# 3x4Matrix.net
KiCad netlist of a schematic drawn in EAGLE
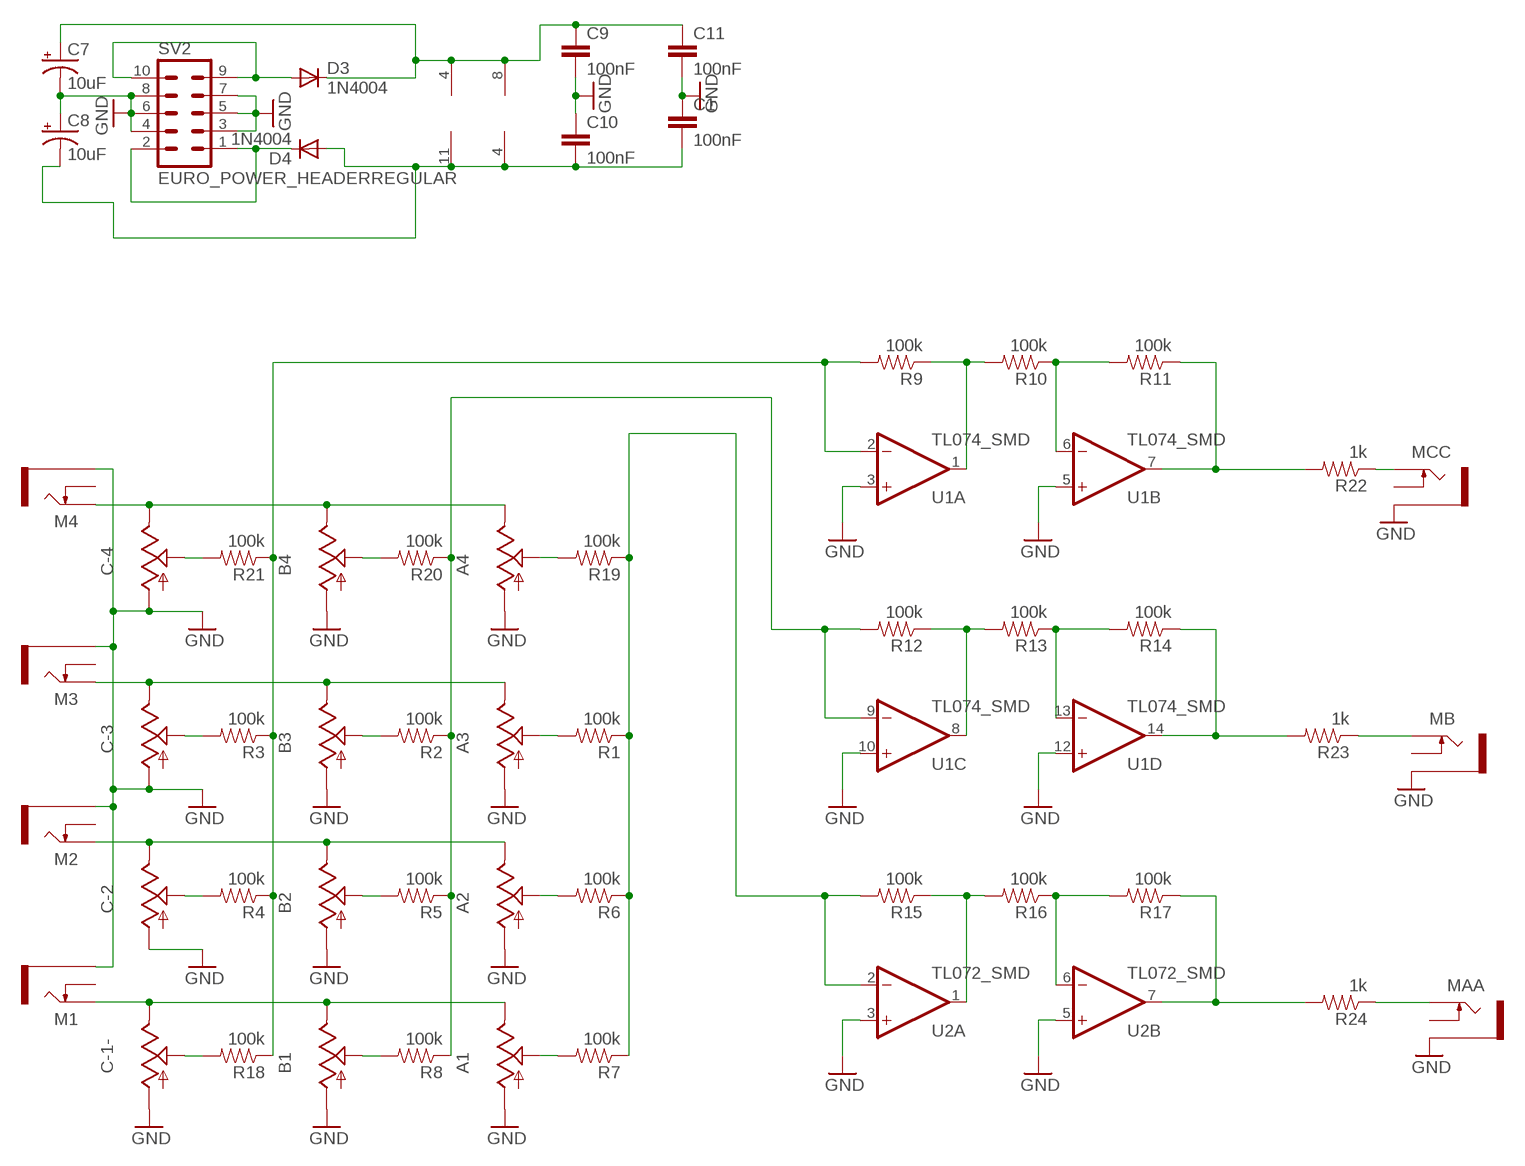
[diagram p0: schematic, sheet 1]

(export (version "E")
  (design (tool "Eeschema 10.0.6"))
  (components
    (comp (ref "A1")
      (value "9MM_SNAP-IN_POT_")
      (footprint "eagle-import:9MM_SNAP-IN_POT")
      (libsource (lib "eagle-import") (part "9MM_SNAP-IN_POT_"))
    )
    (comp (ref "A2")
      (value "9MM_SNAP-IN_POT_")
      (footprint "eagle-import:9MM_SNAP-IN_POT")
      (libsource (lib "eagle-import") (part "9MM_SNAP-IN_POT_"))
    )
    (comp (ref "A3")
      (value "9MM_SNAP-IN_POT_")
      (footprint "eagle-import:9MM_SNAP-IN_POT")
      (libsource (lib "eagle-import") (part "9MM_SNAP-IN_POT_"))
    )
    (comp (ref "A4")
      (value "9MM_SNAP-IN_POT_")
      (footprint "eagle-import:9MM_SNAP-IN_POT")
      (libsource (lib "eagle-import") (part "9MM_SNAP-IN_POT_"))
    )
    (comp (ref "B1")
      (value "9MM_SNAP-IN_POT_")
      (footprint "eagle-import:9MM_SNAP-IN_POT")
      (libsource (lib "eagle-import") (part "9MM_SNAP-IN_POT_"))
    )
    (comp (ref "B2")
      (value "9MM_SNAP-IN_POT_")
      (footprint "eagle-import:9MM_SNAP-IN_POT")
      (libsource (lib "eagle-import") (part "9MM_SNAP-IN_POT_"))
    )
    (comp (ref "B3")
      (value "9MM_SNAP-IN_POT_")
      (footprint "eagle-import:9MM_SNAP-IN_POT")
      (libsource (lib "eagle-import") (part "9MM_SNAP-IN_POT_"))
    )
    (comp (ref "B4")
      (value "9MM_SNAP-IN_POT_")
      (footprint "eagle-import:9MM_SNAP-IN_POT")
      (libsource (lib "eagle-import") (part "9MM_SNAP-IN_POT_"))
    )
    (comp (ref "C-1-")
      (value "9MM_SNAP-IN_POT_")
      (footprint "eagle-import:9MM_SNAP-IN_POT")
      (libsource (lib "eagle-import") (part "9MM_SNAP-IN_POT_"))
    )
    (comp (ref "C-2")
      (value "9MM_SNAP-IN_POT_")
      (footprint "eagle-import:9MM_SNAP-IN_POT")
      (libsource (lib "eagle-import") (part "9MM_SNAP-IN_POT_"))
    )
    (comp (ref "C-3")
      (value "9MM_SNAP-IN_POT_")
      (footprint "eagle-import:9MM_SNAP-IN_POT")
      (libsource (lib "eagle-import") (part "9MM_SNAP-IN_POT_"))
    )
    (comp (ref "C-4")
      (value "9MM_SNAP-IN_POT_")
      (footprint "eagle-import:9MM_SNAP-IN_POT")
      (libsource (lib "eagle-import") (part "9MM_SNAP-IN_POT_"))
    )
    (comp (ref "C1")
      (value "100nF")
      (footprint "eagle-import:0805")
      (libsource (lib "eagle-import") (part "CAP0805"))
    )
    (comp (ref "C7")
      (value "10uF")
      (footprint "eagle-import:CPOL-RADIAL-10UF-25V")
      (libsource (lib "eagle-import") (part "CAP_POLPTH2"))
    )
    (comp (ref "C8")
      (value "10uF")
      (footprint "eagle-import:CPOL-RADIAL-10UF-25V")
      (libsource (lib "eagle-import") (part "CAP_POLPTH2"))
    )
    (comp (ref "C9")
      (value "100nF")
      (footprint "eagle-import:0805")
      (libsource (lib "eagle-import") (part "CAP0805"))
    )
    (comp (ref "C10")
      (value "100nF")
      (footprint "eagle-import:0805")
      (libsource (lib "eagle-import") (part "CAP0805"))
    )
    (comp (ref "C11")
      (value "100nF")
      (footprint "eagle-import:0805")
      (libsource (lib "eagle-import") (part "CAP0805"))
    )
    (comp (ref "D3")
      (value "1N4004")
      (footprint "eagle-import:DO41-10")
      (libsource (lib "eagle-import") (part "1N4004"))
    )
    (comp (ref "D4")
      (value "1N4004")
      (footprint "eagle-import:DO41-10")
      (libsource (lib "eagle-import") (part "1N4004"))
    )
    (comp (ref "M1")
      (value "THONKICONNNEW")
      (footprint "eagle-import:WQP-PJ301M-12_JACK")
      (libsource (lib "eagle-import") (part "THONKICONNNEW"))
    )
    (comp (ref "M2")
      (value "THONKICONNNEW")
      (footprint "eagle-import:WQP-PJ301M-12_JACK")
      (libsource (lib "eagle-import") (part "THONKICONNNEW"))
    )
    (comp (ref "M3")
      (value "THONKICONNNEW")
      (footprint "eagle-import:WQP-PJ301M-12_JACK")
      (libsource (lib "eagle-import") (part "THONKICONNNEW"))
    )
    (comp (ref "M4")
      (value "THONKICONNNEW")
      (footprint "eagle-import:WQP-PJ301M-12_JACK")
      (libsource (lib "eagle-import") (part "THONKICONNNEW"))
    )
    (comp (ref "MAA")
      (value "THONKICONNNEW")
      (footprint "eagle-import:WQP-PJ301M-12_JACK")
      (libsource (lib "eagle-import") (part "THONKICONNNEW"))
    )
    (comp (ref "MB")
      (value "THONKICONNNEW")
      (footprint "eagle-import:WQP-PJ301M-12_JACK")
      (libsource (lib "eagle-import") (part "THONKICONNNEW"))
    )
    (comp (ref "MCC")
      (value "THONKICONNNEW")
      (footprint "eagle-import:WQP-PJ301M-12_JACK")
      (libsource (lib "eagle-import") (part "THONKICONNNEW"))
    )
    (comp (ref "R1")
      (value "100k")
      (footprint "eagle-import:0805")
      (libsource (lib "eagle-import") (part "RESISTOR0805-RES"))
    )
    (comp (ref "R2")
      (value "100k")
      (footprint "eagle-import:0805")
      (libsource (lib "eagle-import") (part "RESISTOR0805-RES"))
    )
    (comp (ref "R3")
      (value "100k")
      (footprint "eagle-import:0805")
      (libsource (lib "eagle-import") (part "RESISTOR0805-RES"))
    )
    (comp (ref "R4")
      (value "100k")
      (footprint "eagle-import:0805")
      (libsource (lib "eagle-import") (part "RESISTOR0805-RES"))
    )
    (comp (ref "R5")
      (value "100k")
      (footprint "eagle-import:0805")
      (libsource (lib "eagle-import") (part "RESISTOR0805-RES"))
    )
    (comp (ref "R6")
      (value "100k")
      (footprint "eagle-import:0805")
      (libsource (lib "eagle-import") (part "RESISTOR0805-RES"))
    )
    (comp (ref "R7")
      (value "100k")
      (footprint "eagle-import:0805")
      (libsource (lib "eagle-import") (part "RESISTOR0805-RES"))
    )
    (comp (ref "R8")
      (value "100k")
      (footprint "eagle-import:0805")
      (libsource (lib "eagle-import") (part "RESISTOR0805-RES"))
    )
    (comp (ref "R9")
      (value "100k")
      (footprint "eagle-import:0805")
      (libsource (lib "eagle-import") (part "RESISTOR0805-RES"))
    )
    (comp (ref "R10")
      (value "100k")
      (footprint "eagle-import:0805")
      (libsource (lib "eagle-import") (part "RESISTOR0805-RES"))
    )
    (comp (ref "R11")
      (value "100k")
      (footprint "eagle-import:0805")
      (libsource (lib "eagle-import") (part "RESISTOR0805-RES"))
    )
    (comp (ref "R12")
      (value "100k")
      (footprint "eagle-import:0805")
      (libsource (lib "eagle-import") (part "RESISTOR0805-RES"))
    )
    (comp (ref "R13")
      (value "100k")
      (footprint "eagle-import:0805")
      (libsource (lib "eagle-import") (part "RESISTOR0805-RES"))
    )
    (comp (ref "R14")
      (value "100k")
      (footprint "eagle-import:0805")
      (libsource (lib "eagle-import") (part "RESISTOR0805-RES"))
    )
    (comp (ref "R15")
      (value "100k")
      (footprint "eagle-import:0805")
      (libsource (lib "eagle-import") (part "RESISTOR0805-RES"))
    )
    (comp (ref "R16")
      (value "100k")
      (footprint "eagle-import:0805")
      (libsource (lib "eagle-import") (part "RESISTOR0805-RES"))
    )
    (comp (ref "R17")
      (value "100k")
      (footprint "eagle-import:0805")
      (libsource (lib "eagle-import") (part "RESISTOR0805-RES"))
    )
    (comp (ref "R18")
      (value "100k")
      (footprint "eagle-import:0805")
      (libsource (lib "eagle-import") (part "RESISTOR0805-RES"))
    )
    (comp (ref "R19")
      (value "100k")
      (footprint "eagle-import:0805")
      (libsource (lib "eagle-import") (part "RESISTOR0805-RES"))
    )
    (comp (ref "R20")
      (value "100k")
      (footprint "eagle-import:0805")
      (libsource (lib "eagle-import") (part "RESISTOR0805-RES"))
    )
    (comp (ref "R21")
      (value "100k")
      (footprint "eagle-import:0805")
      (libsource (lib "eagle-import") (part "RESISTOR0805-RES"))
    )
    (comp (ref "R22")
      (value "1k")
      (footprint "eagle-import:0805")
      (libsource (lib "eagle-import") (part "RESISTOR0805-RES"))
    )
    (comp (ref "R23")
      (value "1k")
      (footprint "eagle-import:0805")
      (libsource (lib "eagle-import") (part "RESISTOR0805-RES"))
    )
    (comp (ref "R24")
      (value "1k")
      (footprint "eagle-import:0805")
      (libsource (lib "eagle-import") (part "RESISTOR0805-RES"))
    )
    (comp (ref "SV2")
      (value "EURO_POWER_HEADERREGULAR")
      (footprint "eagle-import:EURO_POWER_HEADER")
      (libsource (lib "eagle-import") (part "EURO_POWER_HEADERREGULAR"))
    )
    (comp (ref "U1")
      (value "TL074_SMD")
      (footprint "eagle-import:SO14")
      (libsource (lib "eagle-import") (part "TL074_SMD"))
    )
    (comp (ref "U2")
      (value "TL072_SMD")
      (footprint "eagle-import:SO08")
      (libsource (lib "eagle-import") (part "TL072_SMD"))
    )
  )
  (nets
    (net (code "1") (name "GND") (class "Default")
      (node (ref "A1") (pin "1") (pinfunction "A_1") (pintype "passive"))
      (node (ref "A2") (pin "1") (pinfunction "A_1") (pintype "passive"))
      (node (ref "A3") (pin "1") (pinfunction "A_1") (pintype "passive"))
      (node (ref "A4") (pin "1") (pinfunction "A_1") (pintype "passive"))
      (node (ref "B1") (pin "1") (pinfunction "A_1") (pintype "passive"))
      (node (ref "B2") (pin "1") (pinfunction "A_1") (pintype "passive"))
      (node (ref "B3") (pin "1") (pinfunction "A_1") (pintype "passive"))
      (node (ref "B4") (pin "1") (pinfunction "A_1") (pintype "passive"))
      (node (ref "C-1-") (pin "1") (pinfunction "A_1") (pintype "passive"))
      (node (ref "C-2") (pin "1") (pinfunction "A_1") (pintype "passive"))
      (node (ref "C-3") (pin "1") (pinfunction "A_1") (pintype "passive"))
      (node (ref "C-4") (pin "1") (pinfunction "A_1") (pintype "passive"))
      (node (ref "C1") (pin "1") (pinfunction "1_1") (pintype "passive"))
      (node (ref "C10") (pin "1") (pinfunction "1_1") (pintype "passive"))
      (node (ref "C11") (pin "2") (pinfunction "2_2") (pintype "passive"))
      (node (ref "C7") (pin "2") (pinfunction "-_2") (pintype "passive"))
      (node (ref "C8") (pin "1") (pinfunction "+_1") (pintype "passive"))
      (node (ref "C9") (pin "2") (pinfunction "2_2") (pintype "passive"))
      (node (ref "M1") (pin "P$3_SLEEVE") (pinfunction "SLEEVE_P$3_SLEEVE") (pintype "passive"))
      (node (ref "M2") (pin "P$3_SLEEVE") (pinfunction "SLEEVE_P$3_SLEEVE") (pintype "passive"))
      (node (ref "M3") (pin "P$3_SLEEVE") (pinfunction "SLEEVE_P$3_SLEEVE") (pintype "passive"))
      (node (ref "M4") (pin "P$3_SLEEVE") (pinfunction "SLEEVE_P$3_SLEEVE") (pintype "passive"))
      (node (ref "MAA") (pin "P$3_SLEEVE") (pinfunction "SLEEVE_P$3_SLEEVE") (pintype "passive"))
      (node (ref "MB") (pin "P$3_SLEEVE") (pinfunction "SLEEVE_P$3_SLEEVE") (pintype "passive"))
      (node (ref "MCC") (pin "P$3_SLEEVE") (pinfunction "SLEEVE_P$3_SLEEVE") (pintype "passive"))
      (node (ref "SV2") (pin "3") (pinfunction "3_3") (pintype "passive"))
      (node (ref "SV2") (pin "4") (pinfunction "4_4") (pintype "passive"))
      (node (ref "SV2") (pin "5") (pinfunction "5_5") (pintype "passive"))
      (node (ref "SV2") (pin "6") (pinfunction "6_6") (pintype "passive"))
      (node (ref "SV2") (pin "7") (pinfunction "7_7") (pintype "passive"))
      (node (ref "SV2") (pin "8") (pinfunction "8_8") (pintype "passive"))
      (node (ref "U1") (pin "10") (pinfunction "+IN_10") (pintype "input"))
      (node (ref "U1") (pin "12") (pinfunction "+IN_12") (pintype "input"))
      (node (ref "U1") (pin "3") (pinfunction "+IN_3") (pintype "input"))
      (node (ref "U1") (pin "5") (pinfunction "+IN_5") (pintype "input"))
      (node (ref "U2") (pin "3") (pinfunction "+IN_3") (pintype "input"))
      (node (ref "U2") (pin "5") (pinfunction "+IN_5") (pintype "input"))
    )
    (net (code "2") (name "Net-(A1-E)") (class "Default")
      (node (ref "A1") (pin "3") (pinfunction "E_3") (pintype "passive"))
      (node (ref "B1") (pin "3") (pinfunction "E_3") (pintype "passive"))
      (node (ref "C-1-") (pin "3") (pinfunction "E_3") (pintype "passive"))
      (node (ref "M1") (pin "P$1_TIP") (pinfunction "TIP_P$1_TIP") (pintype "passive"))
    )
    (net (code "3") (name "Net-(A1-S)") (class "Default")
      (node (ref "A1") (pin "2") (pinfunction "S_2") (pintype "passive"))
      (node (ref "R7") (pin "2") (pinfunction "2_2") (pintype "passive"))
    )
    (net (code "4") (name "Net-(A2-E)") (class "Default")
      (node (ref "A2") (pin "3") (pinfunction "E_3") (pintype "passive"))
      (node (ref "B2") (pin "3") (pinfunction "E_3") (pintype "passive"))
      (node (ref "C-2") (pin "3") (pinfunction "E_3") (pintype "passive"))
      (node (ref "M2") (pin "P$1_TIP") (pinfunction "TIP_P$1_TIP") (pintype "passive"))
    )
    (net (code "5") (name "Net-(A2-S)") (class "Default")
      (node (ref "A2") (pin "2") (pinfunction "S_2") (pintype "passive"))
      (node (ref "R6") (pin "2") (pinfunction "2_2") (pintype "passive"))
    )
    (net (code "6") (name "Net-(A3-E)") (class "Default")
      (node (ref "A3") (pin "3") (pinfunction "E_3") (pintype "passive"))
      (node (ref "B3") (pin "3") (pinfunction "E_3") (pintype "passive"))
      (node (ref "C-3") (pin "3") (pinfunction "E_3") (pintype "passive"))
      (node (ref "M3") (pin "P$1_TIP") (pinfunction "TIP_P$1_TIP") (pintype "passive"))
    )
    (net (code "7") (name "Net-(A3-S)") (class "Default")
      (node (ref "A3") (pin "2") (pinfunction "S_2") (pintype "passive"))
      (node (ref "R1") (pin "2") (pinfunction "2_2") (pintype "passive"))
    )
    (net (code "8") (name "Net-(A4-E)") (class "Default")
      (node (ref "A4") (pin "3") (pinfunction "E_3") (pintype "passive"))
      (node (ref "B4") (pin "3") (pinfunction "E_3") (pintype "passive"))
      (node (ref "C-4") (pin "3") (pinfunction "E_3") (pintype "passive"))
      (node (ref "M4") (pin "P$1_TIP") (pinfunction "TIP_P$1_TIP") (pintype "passive"))
    )
    (net (code "9") (name "Net-(A4-S)") (class "Default")
      (node (ref "A4") (pin "2") (pinfunction "S_2") (pintype "passive"))
      (node (ref "R19") (pin "2") (pinfunction "2_2") (pintype "passive"))
    )
    (net (code "10") (name "Net-(B1-S)") (class "Default")
      (node (ref "B1") (pin "2") (pinfunction "S_2") (pintype "passive"))
      (node (ref "R8") (pin "2") (pinfunction "2_2") (pintype "passive"))
    )
    (net (code "11") (name "Net-(B2-S)") (class "Default")
      (node (ref "B2") (pin "2") (pinfunction "S_2") (pintype "passive"))
      (node (ref "R5") (pin "2") (pinfunction "2_2") (pintype "passive"))
    )
    (net (code "12") (name "Net-(B3-S)") (class "Default")
      (node (ref "B3") (pin "2") (pinfunction "S_2") (pintype "passive"))
      (node (ref "R2") (pin "2") (pinfunction "2_2") (pintype "passive"))
    )
    (net (code "13") (name "Net-(B4-S)") (class "Default")
      (node (ref "B4") (pin "2") (pinfunction "S_2") (pintype "passive"))
      (node (ref "R20") (pin "2") (pinfunction "2_2") (pintype "passive"))
    )
    (net (code "14") (name "Net-(C-1--S)") (class "Default")
      (node (ref "C-1-") (pin "2") (pinfunction "S_2") (pintype "passive"))
      (node (ref "R18") (pin "2") (pinfunction "2_2") (pintype "passive"))
    )
    (net (code "15") (name "Net-(C-2-S)") (class "Default")
      (node (ref "C-2") (pin "2") (pinfunction "S_2") (pintype "passive"))
      (node (ref "R4") (pin "2") (pinfunction "2_2") (pintype "passive"))
    )
    (net (code "16") (name "Net-(C-3-S)") (class "Default")
      (node (ref "C-3") (pin "2") (pinfunction "S_2") (pintype "passive"))
      (node (ref "R3") (pin "2") (pinfunction "2_2") (pintype "passive"))
    )
    (net (code "17") (name "Net-(C-4-S)") (class "Default")
      (node (ref "C-4") (pin "2") (pinfunction "S_2") (pintype "passive"))
      (node (ref "R21") (pin "2") (pinfunction "2_2") (pintype "passive"))
    )
    (net (code "18") (name "Net-(C7-+)") (class "Default")
      (node (ref "C11") (pin "1") (pinfunction "1_1") (pintype "passive"))
      (node (ref "C7") (pin "1") (pinfunction "+_1") (pintype "passive"))
      (node (ref "C9") (pin "1") (pinfunction "1_1") (pintype "passive"))
      (node (ref "D3") (pin "C") (pinfunction "C_C") (pintype "passive"))
      (node (ref "U1") (pin "4") (pinfunction "V+_4") (pintype "power_in"))
      (node (ref "U2") (pin "8") (pinfunction "V+_8") (pintype "power_in"))
    )
    (net (code "19") (name "Net-(C8--)") (class "Default")
      (node (ref "C1") (pin "2") (pinfunction "2_2") (pintype "passive"))
      (node (ref "C10") (pin "2") (pinfunction "2_2") (pintype "passive"))
      (node (ref "C8") (pin "2") (pinfunction "-_2") (pintype "passive"))
      (node (ref "D4") (pin "A") (pinfunction "A_A") (pintype "passive"))
      (node (ref "U1") (pin "11") (pinfunction "V-_11") (pintype "power_in"))
      (node (ref "U2") (pin "4") (pinfunction "V-_4") (pintype "power_in"))
    )
    (net (code "20") (name "Net-(D3-PadA)") (class "Default")
      (node (ref "D3") (pin "A") (pinfunction "A_A") (pintype "passive"))
      (node (ref "SV2") (pin "10") (pinfunction "10_10") (pintype "passive"))
      (node (ref "SV2") (pin "9") (pinfunction "9_9") (pintype "passive"))
    )
    (net (code "21") (name "Net-(D4-PadC)") (class "Default")
      (node (ref "D4") (pin "C") (pinfunction "C_C") (pintype "passive"))
      (node (ref "SV2") (pin "1") (pinfunction "1_1") (pintype "passive"))
      (node (ref "SV2") (pin "2") (pinfunction "2_2") (pintype "passive"))
    )
    (net (code "22") (name "Net-(MAA-TIP)") (class "Default")
      (node (ref "MAA") (pin "P$1_TIP") (pinfunction "TIP_P$1_TIP") (pintype "passive"))
      (node (ref "R24") (pin "1") (pinfunction "1_1") (pintype "passive"))
    )
    (net (code "23") (name "Net-(MB-TIP)") (class "Default")
      (node (ref "MB") (pin "P$1_TIP") (pinfunction "TIP_P$1_TIP") (pintype "passive"))
      (node (ref "R23") (pin "1") (pinfunction "1_1") (pintype "passive"))
    )
    (net (code "24") (name "Net-(MCC-TIP)") (class "Default")
      (node (ref "MCC") (pin "P$1_TIP") (pinfunction "TIP_P$1_TIP") (pintype "passive"))
      (node (ref "R22") (pin "1") (pinfunction "1_1") (pintype "passive"))
    )
    (net (code "25") (name "Net-(U1A--IN)") (class "Default")
      (node (ref "R18") (pin "1") (pinfunction "1_1") (pintype "passive"))
      (node (ref "R21") (pin "1") (pinfunction "1_1") (pintype "passive"))
      (node (ref "R3") (pin "1") (pinfunction "1_1") (pintype "passive"))
      (node (ref "R4") (pin "1") (pinfunction "1_1") (pintype "passive"))
      (node (ref "R9") (pin "2") (pinfunction "2_2") (pintype "passive"))
      (node (ref "U1") (pin "2") (pinfunction "-IN_2") (pintype "input"))
    )
    (net (code "26") (name "Net-(U1A-OUT)") (class "Default")
      (node (ref "R10") (pin "2") (pinfunction "2_2") (pintype "passive"))
      (node (ref "R9") (pin "1") (pinfunction "1_1") (pintype "passive"))
      (node (ref "U1") (pin "1") (pinfunction "OUT_1") (pintype "output"))
    )
    (net (code "27") (name "Net-(U1B--IN)") (class "Default")
      (node (ref "R10") (pin "1") (pinfunction "1_1") (pintype "passive"))
      (node (ref "R11") (pin "2") (pinfunction "2_2") (pintype "passive"))
      (node (ref "U1") (pin "6") (pinfunction "-IN_6") (pintype "input"))
    )
    (net (code "28") (name "Net-(U1B-OUT)") (class "Default")
      (node (ref "R11") (pin "1") (pinfunction "1_1") (pintype "passive"))
      (node (ref "R22") (pin "2") (pinfunction "2_2") (pintype "passive"))
      (node (ref "U1") (pin "7") (pinfunction "OUT_7") (pintype "output"))
    )
    (net (code "29") (name "Net-(U1C--IN)") (class "Default")
      (node (ref "R12") (pin "2") (pinfunction "2_2") (pintype "passive"))
      (node (ref "R2") (pin "1") (pinfunction "1_1") (pintype "passive"))
      (node (ref "R20") (pin "1") (pinfunction "1_1") (pintype "passive"))
      (node (ref "R5") (pin "1") (pinfunction "1_1") (pintype "passive"))
      (node (ref "R8") (pin "1") (pinfunction "1_1") (pintype "passive"))
      (node (ref "U1") (pin "9") (pinfunction "-IN_9") (pintype "input"))
    )
    (net (code "30") (name "Net-(U1C-OUT)") (class "Default")
      (node (ref "R12") (pin "1") (pinfunction "1_1") (pintype "passive"))
      (node (ref "R13") (pin "2") (pinfunction "2_2") (pintype "passive"))
      (node (ref "U1") (pin "8") (pinfunction "OUT_8") (pintype "output"))
    )
    (net (code "31") (name "Net-(U1D--IN)") (class "Default")
      (node (ref "R13") (pin "1") (pinfunction "1_1") (pintype "passive"))
      (node (ref "R14") (pin "2") (pinfunction "2_2") (pintype "passive"))
      (node (ref "U1") (pin "13") (pinfunction "-IN_13") (pintype "input"))
    )
    (net (code "32") (name "Net-(U1D-OUT)") (class "Default")
      (node (ref "R14") (pin "1") (pinfunction "1_1") (pintype "passive"))
      (node (ref "R23") (pin "2") (pinfunction "2_2") (pintype "passive"))
      (node (ref "U1") (pin "14") (pinfunction "OUT_14") (pintype "output"))
    )
    (net (code "33") (name "Net-(U2A--IN)") (class "Default")
      (node (ref "R1") (pin "1") (pinfunction "1_1") (pintype "passive"))
      (node (ref "R15") (pin "2") (pinfunction "2_2") (pintype "passive"))
      (node (ref "R19") (pin "1") (pinfunction "1_1") (pintype "passive"))
      (node (ref "R6") (pin "1") (pinfunction "1_1") (pintype "passive"))
      (node (ref "R7") (pin "1") (pinfunction "1_1") (pintype "passive"))
      (node (ref "U2") (pin "2") (pinfunction "-IN_2") (pintype "input"))
    )
    (net (code "34") (name "Net-(U2A-OUT)") (class "Default")
      (node (ref "R15") (pin "1") (pinfunction "1_1") (pintype "passive"))
      (node (ref "R16") (pin "2") (pinfunction "2_2") (pintype "passive"))
      (node (ref "U2") (pin "1") (pinfunction "OUT_1") (pintype "output"))
    )
    (net (code "35") (name "Net-(U2B--IN)") (class "Default")
      (node (ref "R16") (pin "1") (pinfunction "1_1") (pintype "passive"))
      (node (ref "R17") (pin "2") (pinfunction "2_2") (pintype "passive"))
      (node (ref "U2") (pin "6") (pinfunction "-IN_6") (pintype "input"))
    )
    (net (code "36") (name "Net-(U2B-OUT)") (class "Default")
      (node (ref "R17") (pin "1") (pinfunction "1_1") (pintype "passive"))
      (node (ref "R24") (pin "2") (pinfunction "2_2") (pintype "passive"))
      (node (ref "U2") (pin "7") (pinfunction "OUT_7") (pintype "output"))
    )
    (net (code "37") (name "unconnected-(M1-SWITCH-PadP$2_SWITCH)") (class "Default")
      (node (ref "M1") (pin "P$2_SWITCH") (pinfunction "SWITCH_P$2_SWITCH") (pintype "passive"))
    )
    (net (code "38") (name "unconnected-(M2-SWITCH-PadP$2_SWITCH)") (class "Default")
      (node (ref "M2") (pin "P$2_SWITCH") (pinfunction "SWITCH_P$2_SWITCH") (pintype "passive"))
    )
    (net (code "39") (name "unconnected-(M3-SWITCH-PadP$2_SWITCH)") (class "Default")
      (node (ref "M3") (pin "P$2_SWITCH") (pinfunction "SWITCH_P$2_SWITCH") (pintype "passive"))
    )
    (net (code "40") (name "unconnected-(M4-SWITCH-PadP$2_SWITCH)") (class "Default")
      (node (ref "M4") (pin "P$2_SWITCH") (pinfunction "SWITCH_P$2_SWITCH") (pintype "passive"))
    )
    (net (code "41") (name "unconnected-(MAA-SWITCH-PadP$2_SWITCH)") (class "Default")
      (node (ref "MAA") (pin "P$2_SWITCH") (pinfunction "SWITCH_P$2_SWITCH") (pintype "passive"))
    )
    (net (code "42") (name "unconnected-(MB-SWITCH-PadP$2_SWITCH)") (class "Default")
      (node (ref "MB") (pin "P$2_SWITCH") (pinfunction "SWITCH_P$2_SWITCH") (pintype "passive"))
    )
    (net (code "43") (name "unconnected-(MCC-SWITCH-PadP$2_SWITCH)") (class "Default")
      (node (ref "MCC") (pin "P$2_SWITCH") (pinfunction "SWITCH_P$2_SWITCH") (pintype "passive"))
    )
  )
)
